# PA_Channel.net
KiCad netlist of a schematic drawn in Altium Designer
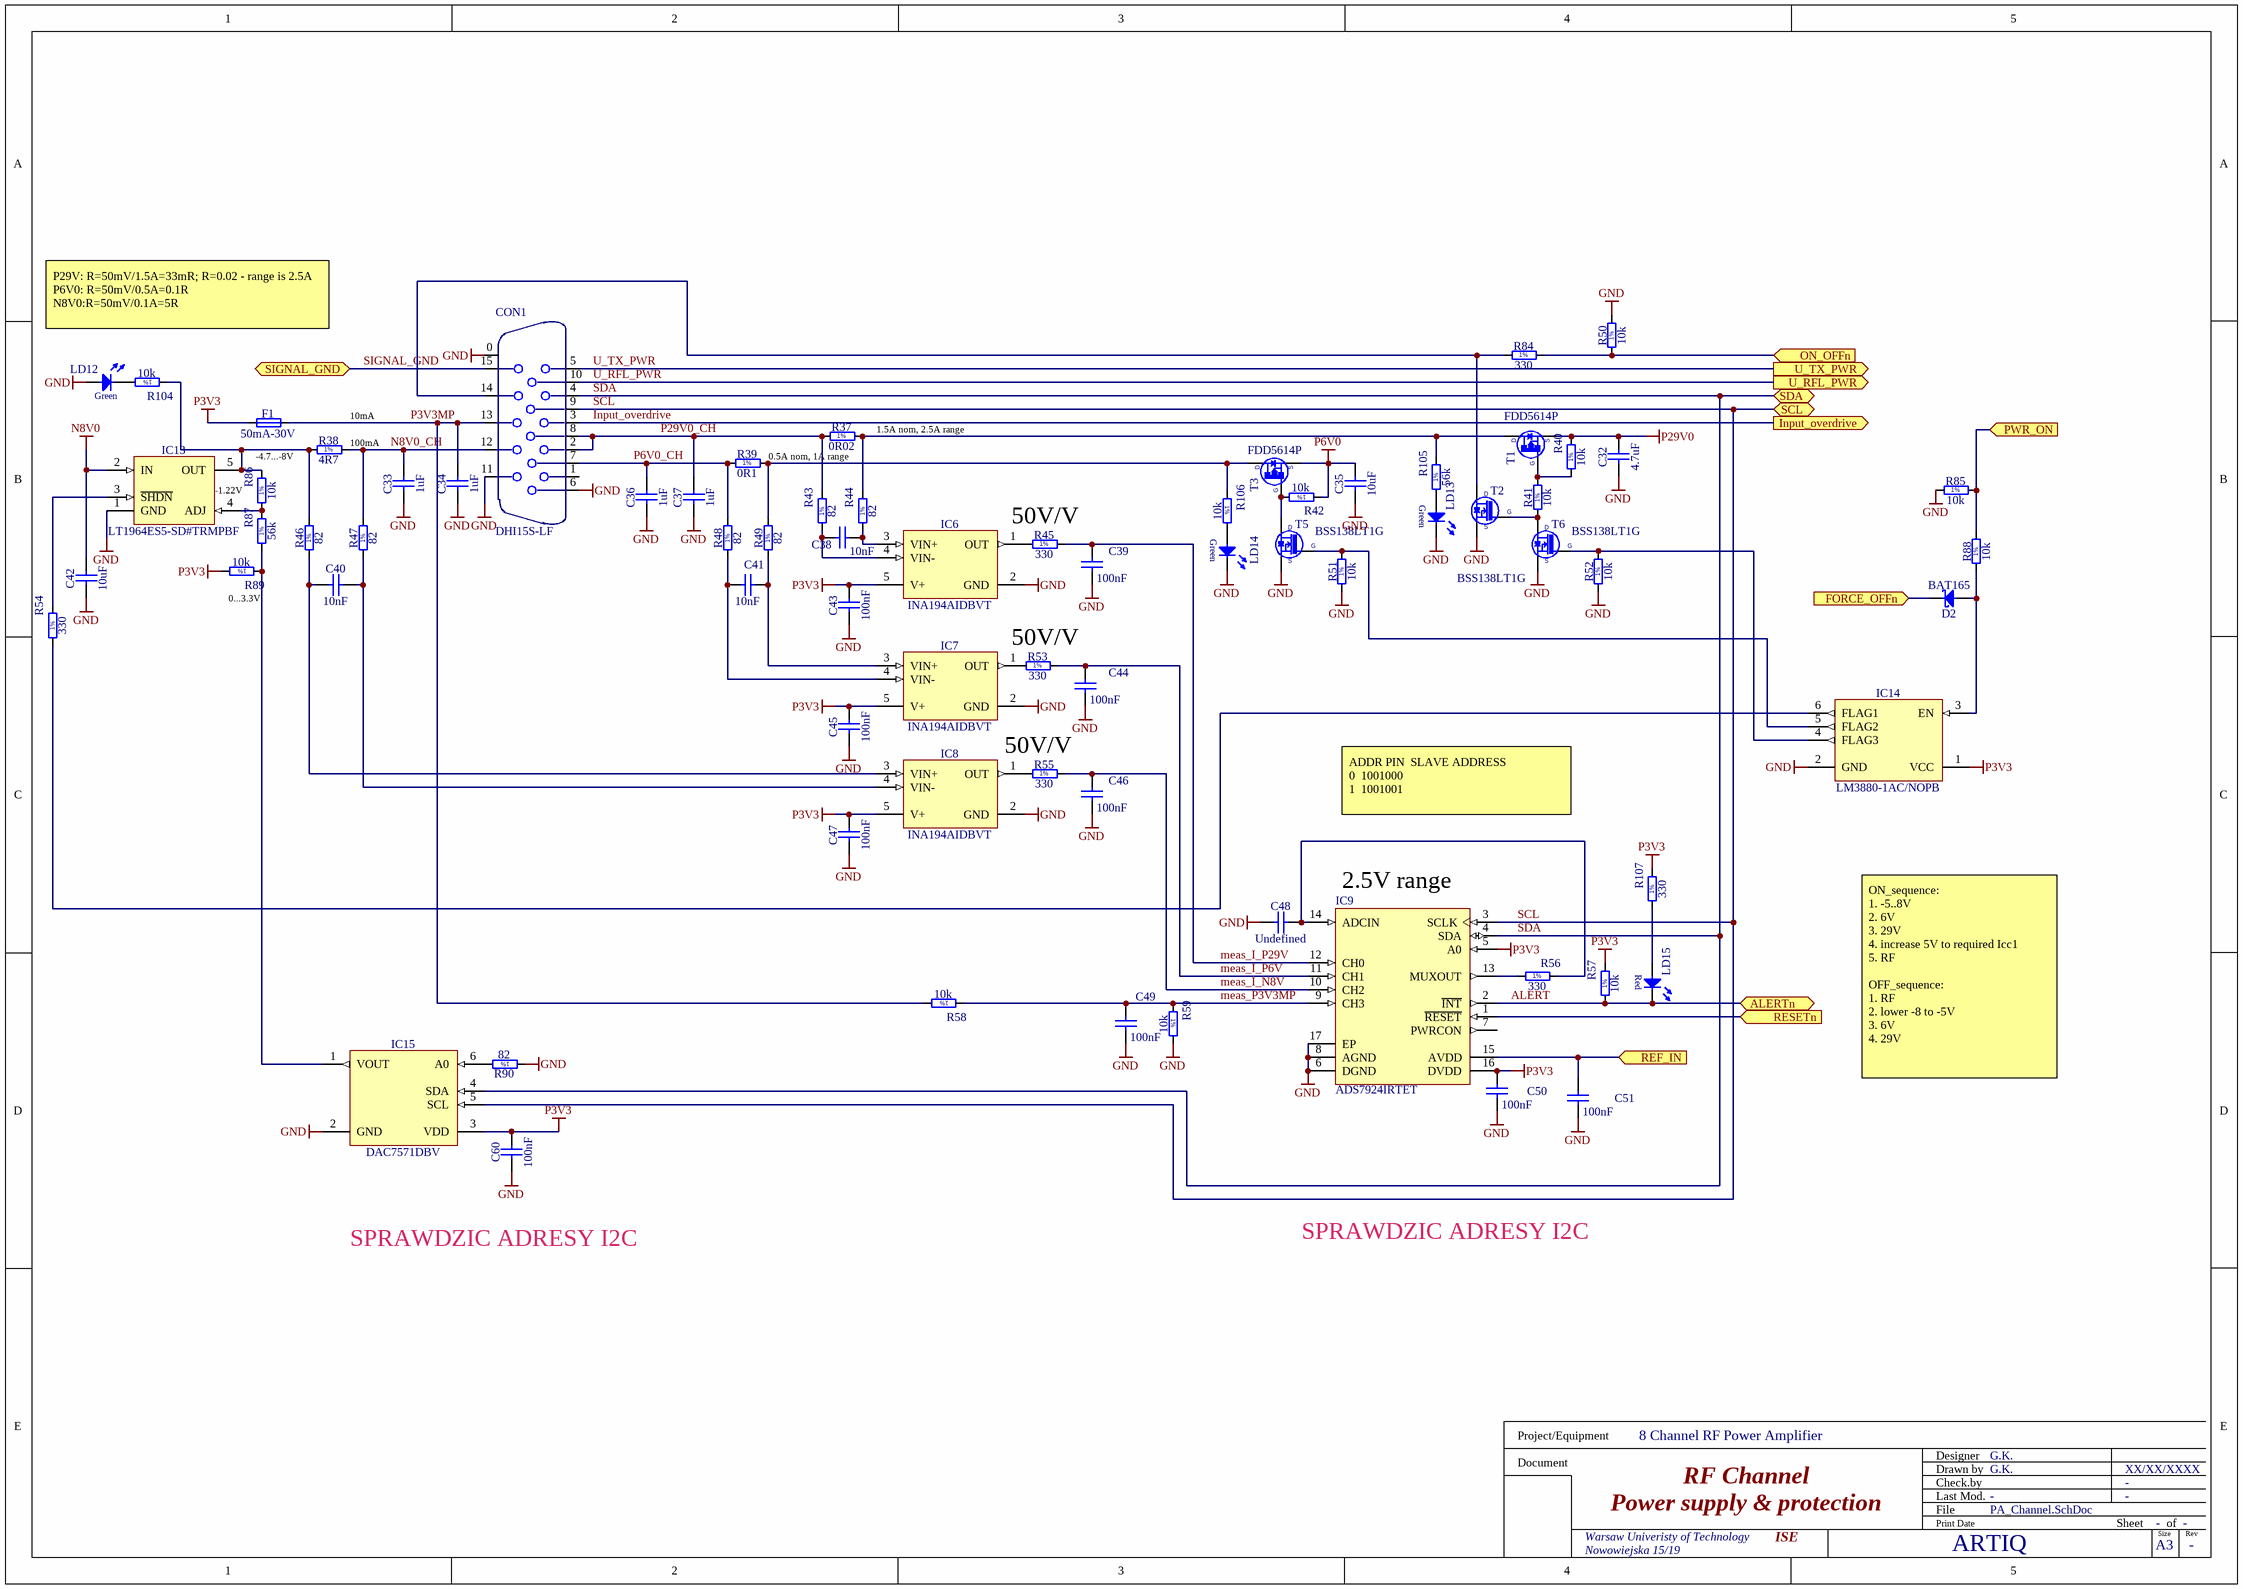
[diagram p0: PA_Channel.SchDoc]

(export (version "E")
  (design (tool "Eeschema 10.0.6"))
  (components
    (comp (ref "C32")
      (value "4.7uF")
      (footprint "CAPC3216X180N")
      (description "Non-polarised capacitor")
      (fields
        (field (name "PART NUMBER") "CC1206_4.7UF_50V_+80%-20%_Y5V")
        (field (name "VOLTAGE") "50V")
        (field (name "AUTHOR") "CERN DEM JLC")
      )
      (libsource (lib "Capacitors") (part "Capacitor - non polarized"))
    )
    (comp (ref "C33")
      (value "1uF")
      (footprint "CAPC2012X110N")
      (description "Non-polarised capacitor")
      (fields
        (field (name "PART NUMBER") "CC0805_1UF_50V_10%_X7R")
        (field (name "VOLTAGE") "50V")
        (field (name "AUTHOR") "CERN DEM JLC")
      )
      (libsource (lib "Capacitors") (part "Capacitor - non polarized"))
    )
    (comp (ref "C34")
      (value "1uF")
      (footprint "CAPC2012X110N")
      (description "Non-polarised capacitor")
      (fields
        (field (name "PART NUMBER") "CC0805_1UF_50V_10%_X7R")
        (field (name "VOLTAGE") "50V")
        (field (name "AUTHOR") "CERN DEM JLC")
      )
      (libsource (lib "Capacitors") (part "Capacitor - non polarized"))
    )
    (comp (ref "C35")
      (value "10uF")
      (footprint "CAPC3216X140N")
      (description "Non-polarised capacitor")
      (fields
        (field (name "PART NUMBER") "CC1206_10UF_16V_10%_X7R")
        (field (name "VOLTAGE") "16V")
        (field (name "AUTHOR") "CERN DEM JLC")
      )
      (libsource (lib "Capacitors") (part "Capacitor - non polarized"))
    )
    (comp (ref "C36")
      (value "1uF")
      (footprint "CAPC2012X110N")
      (description "Non-polarised capacitor")
      (fields
        (field (name "PART NUMBER") "CC0805_1UF_50V_10%_X7R")
        (field (name "VOLTAGE") "50V")
        (field (name "AUTHOR") "CERN DEM JLC")
      )
      (libsource (lib "Capacitors") (part "Capacitor - non polarized"))
    )
    (comp (ref "C37")
      (value "1uF")
      (footprint "CAPC2012X110N")
      (description "Non-polarised capacitor")
      (fields
        (field (name "PART NUMBER") "CC0805_1UF_50V_10%_X7R")
        (field (name "VOLTAGE") "50V")
        (field (name "AUTHOR") "CERN DEM JLC")
      )
      (libsource (lib "Capacitors") (part "Capacitor - non polarized"))
    )
    (comp (ref "C38")
      (value "10nF")
      (footprint "CAPC1608X87N")
      (description "Non-polarised capacitor")
      (fields
        (field (name "PART NUMBER") "CC0603_10NF_50V_5%_C0G")
        (field (name "VOLTAGE") "50V")
        (field (name "AUTHOR") "CERN DEM JLC")
      )
      (libsource (lib "Capacitors") (part "Capacitor - non polarized"))
    )
    (comp (ref "C39")
      (value "100nF")
      (footprint "CAPC1005X55N")
      (description "Non-polarised capacitor")
      (fields
        (field (name "PART NUMBER") "CC0402_100NF_16V_10%_X7R")
        (field (name "VOLTAGE") "16V")
        (field (name "AUTHOR") "CERN DEM JLC")
      )
      (libsource (lib "Capacitors") (part "Capacitor - non polarized"))
    )
    (comp (ref "C40")
      (value "10nF")
      (footprint "CAPC1608X87N")
      (description "Non-polarised capacitor")
      (fields
        (field (name "PART NUMBER") "CC0603_10NF_50V_5%_C0G")
        (field (name "VOLTAGE") "50V")
        (field (name "AUTHOR") "CERN DEM JLC")
      )
      (libsource (lib "Capacitors") (part "Capacitor - non polarized"))
    )
    (comp (ref "C41")
      (value "10nF")
      (footprint "CAPC1608X87N")
      (description "Non-polarised capacitor")
      (fields
        (field (name "PART NUMBER") "CC0603_10NF_50V_5%_C0G")
        (field (name "VOLTAGE") "50V")
        (field (name "AUTHOR") "CERN DEM JLC")
      )
      (libsource (lib "Capacitors") (part "Capacitor - non polarized"))
    )
    (comp (ref "C42")
      (value "10uF")
      (footprint "CAPC3216X140N")
      (description "Non-polarised capacitor")
      (fields
        (field (name "PART NUMBER") "CC1206_10UF_16V_10%_X7R")
        (field (name "VOLTAGE") "16V")
        (field (name "AUTHOR") "CERN DEM JLC")
      )
      (libsource (lib "Capacitors") (part "Capacitor - non polarized"))
    )
    (comp (ref "C43")
      (value "100nF")
      (footprint "CAPC1005X55N")
      (description "Non-polarised capacitor")
      (fields
        (field (name "PART NUMBER") "CC0402_100NF_16V_10%_X7R")
        (field (name "VOLTAGE") "16V")
        (field (name "AUTHOR") "CERN DEM JLC")
      )
      (libsource (lib "Capacitors") (part "Capacitor - non polarized"))
    )
    (comp (ref "C44")
      (value "100nF")
      (footprint "CAPC1005X55N")
      (description "Non-polarised capacitor")
      (fields
        (field (name "PART NUMBER") "CC0402_100NF_16V_10%_X7R")
        (field (name "VOLTAGE") "16V")
        (field (name "AUTHOR") "CERN DEM JLC")
      )
      (libsource (lib "Capacitors") (part "Capacitor - non polarized"))
    )
    (comp (ref "C45")
      (value "100nF")
      (footprint "CAPC1005X55N")
      (description "Non-polarised capacitor")
      (fields
        (field (name "PART NUMBER") "CC0402_100NF_16V_10%_X7R")
        (field (name "VOLTAGE") "16V")
        (field (name "AUTHOR") "CERN DEM JLC")
      )
      (libsource (lib "Capacitors") (part "Capacitor - non polarized"))
    )
    (comp (ref "C46")
      (value "100nF")
      (footprint "CAPC1005X55N")
      (description "Non-polarised capacitor")
      (fields
        (field (name "PART NUMBER") "CC0402_100NF_16V_10%_X7R")
        (field (name "VOLTAGE") "16V")
        (field (name "AUTHOR") "CERN DEM JLC")
      )
      (libsource (lib "Capacitors") (part "Capacitor - non polarized"))
    )
    (comp (ref "C47")
      (value "100nF")
      (footprint "CAPC1005X55N")
      (description "Non-polarised capacitor")
      (fields
        (field (name "PART NUMBER") "CC0402_100NF_16V_10%_X7R")
        (field (name "VOLTAGE") "16V")
        (field (name "AUTHOR") "CERN DEM JLC")
      )
      (libsource (lib "Capacitors") (part "Capacitor - non polarized"))
    )
    (comp (ref "C48")
      (value "Undefined")
      (footprint "CAPC1005X55N")
      (description "Non-polarised capacitor")
      (fields (field (name "PART NUMBER") "CC0402_NO-VALUE") (field (name "AUTHOR") "CERN DEM JLC"))
      (libsource (lib "Capacitors") (part "Capacitor - non polarized"))
    )
    (comp (ref "C49")
      (value "100nF")
      (footprint "CAPC1005X55N")
      (description "Non-polarised capacitor")
      (fields
        (field (name "PART NUMBER") "CC0402_100NF_16V_10%_X7R")
        (field (name "VOLTAGE") "16V")
        (field (name "AUTHOR") "CERN DEM JLC")
      )
      (libsource (lib "Capacitors") (part "Capacitor - non polarized"))
    )
    (comp (ref "C50")
      (value "100nF")
      (footprint "CAPC1005X55N")
      (description "Non-polarised capacitor")
      (fields
        (field (name "PART NUMBER") "CC0402_100NF_16V_10%_X7R")
        (field (name "VOLTAGE") "16V")
        (field (name "AUTHOR") "CERN DEM JLC")
      )
      (libsource (lib "Capacitors") (part "Capacitor - non polarized"))
    )
    (comp (ref "C51")
      (value "100nF")
      (footprint "CAPC1005X55N")
      (description "Non-polarised capacitor")
      (fields
        (field (name "PART NUMBER") "CC0402_100NF_16V_10%_X7R")
        (field (name "VOLTAGE") "16V")
        (field (name "AUTHOR") "CERN DEM JLC")
      )
      (libsource (lib "Capacitors") (part "Capacitor - non polarized"))
    )
    (comp (ref "C60")
      (value "100nF")
      (footprint "CAPC1005X55N")
      (description "Non-polarised capacitor")
      (fields
        (field (name "PART NUMBER") "CC0402_100NF_16V_10%_X7R")
        (field (name "VOLTAGE") "16V")
        (field (name "AUTHOR") "CERN DEM JLC")
      )
      (libsource (lib "Capacitors") (part "Capacitor - non polarized"))
    )
    (comp (ref "CON1")
      (value "DHI15S-LF")
      (footprint "DB15_HD_V_DHI15S-LF")
      (description "High Density D-SUB (Maritex)")
      (libsource (lib "LIBRARY_SCH") (part "CON_DB15HD_F_V"))
    )
    (comp (ref "D2")
      (value "BAT165")
      (footprint "SOD2512X110N")
      (description "Schottky Diode")
      (fields
        (field (name "VOLTAGE") "40V")
        (field (name "POWER") "750mA")
        (field (name "AUTHOR") "CERN DEM JLC")
      )
      (libsource (lib "ICs And Semiconductors") (part "Diode Schottky"))
    )
    (comp (ref "F1")
      (value "50mA-30V")
      (footprint "FUSRC3226X85N")
      (description "Fuse")
      (fields
        (field (name "PART NUMBER") "FUSR1210_TYCO-MICROSMD005F")
        (field (name "MANUFACTURER") "TYCO ELECTRONICS")
        (field (name "AUTHOR") "CERN DEM JLC")
      )
      (libsource (lib "Eletro-mechanical") (part "Fuse"))
    )
    (comp (ref "IC6")
      (value "INA194AIDBVT")
      (footprint "SOT95P280X145-5N")
      (description "Current Shunt Monitor -16V to +80V Common-Mode Range")
      (fields (field (name "MANUFACTURER") "TEXAS INSTRUMENTS") (field (name "AUTHOR") "CERN DEM JLC"))
      (libsource (lib "ICs And Semiconductors") (part "INA194"))
    )
    (comp (ref "IC7")
      (value "INA194AIDBVT")
      (footprint "SOT95P280X145-5N")
      (description "Current Shunt Monitor -16V to +80V Common-Mode Range")
      (fields (field (name "MANUFACTURER") "TEXAS INSTRUMENTS") (field (name "AUTHOR") "CERN DEM JLC"))
      (libsource (lib "ICs And Semiconductors") (part "INA194"))
    )
    (comp (ref "IC8")
      (value "INA194AIDBVT")
      (footprint "SOT95P280X145-5N")
      (description "Current Shunt Monitor -16V to +80V Common-Mode Range")
      (fields (field (name "MANUFACTURER") "TEXAS INSTRUMENTS") (field (name "AUTHOR") "CERN DEM JLC"))
      (libsource (lib "ICs And Semiconductors") (part "INA194"))
    )
    (comp (ref "IC9")
      (value "ADS7924IRTET")
      (footprint "TI-RTE16-1700X1700TP_V")
      (fields (field (name "MANUFACTURER") "Texas Instruments"))
      (libsource (lib "Altium Content Vault") (part "CMP-0003-02162-1"))
    )
    (comp (ref "IC13")
      (value "LT1964ES5-SD#TRMPBF")
      (footprint "SOT95P280X100-5N")
      (description "200mA, Low Noise, Low Dropout Negative Micropower Regulator")
      (fields (field (name "MANUFACTURER") "LINEAR TECHNOLOGY") (field (name "AUTHOR") "CERN DEM JLC"))
      (libsource (lib "ICs And Semiconductors") (part "LT1964-SD"))
    )
    (comp (ref "IC14")
      (value "LM3880-1AC/NOPB")
      (footprint "SOT95P280X145-6N")
      (description "Simple Power Sequencer")
      (fields (field (name "MANUFACTURER") "TEXAS INSTRUMENTS") (field (name "AUTHOR") "CERN DEM MR"))
      (libsource (lib "ICs And Semiconductors") (part "LM3880"))
    )
    (comp (ref "IC15")
      (value "DAC7571DBV")
      (footprint "SOT95P280X145-6N")
      (description "+2.7 V to +5.5 V, I2C Interface (Receive Only), Voltage Output, 12-Bit Digital-To-Analog Converter")
      (fields (field (name "MANUFACTURER") "TEXAS INSTRUMENTS") (field (name "AUTHOR") "CERN DEM MR"))
      (libsource (lib "ICs And Semiconductors") (part "DAC7571"))
    )
    (comp (ref "LD12")
      (value "Green")
      (footprint "LED_OSRAM_LGL29K")
      (description "LED Green 1C 2A")
      (fields
        (field (name "PART NUMBER") "LED_OSRAM_LG L29K-G2J1-24-Z")
        (field (name "MANUFACTURER") "OSRAM")
        (field (name "AUTHOR") "CERN DEM JLC")
      )
      (libsource (lib "ICs And Semiconductors") (part "LED Green 1C 2A"))
    )
    (comp (ref "LD13")
      (value "Green")
      (footprint "LED_OSRAM_LGL29K")
      (description "LED Green 1C 2A")
      (fields
        (field (name "PART NUMBER") "LED_OSRAM_LG L29K-G2J1-24-Z")
        (field (name "MANUFACTURER") "OSRAM")
        (field (name "AUTHOR") "CERN DEM JLC")
      )
      (libsource (lib "ICs And Semiconductors") (part "LED Green 1C 2A"))
    )
    (comp (ref "LD14")
      (value "Green")
      (footprint "LED_OSRAM_LGL29K")
      (description "LED Green 1C 2A")
      (fields
        (field (name "PART NUMBER") "LED_OSRAM_LG L29K-G2J1-24-Z")
        (field (name "MANUFACTURER") "OSRAM")
        (field (name "AUTHOR") "CERN DEM JLC")
      )
      (libsource (lib "ICs And Semiconductors") (part "LED Green 1C 2A"))
    )
    (comp (ref "LD15")
      (value "Super Red")
      (footprint "LED_OSRAM_LS Q976")
      (description "LED Red 1C 2A")
      (fields
        (field (name "PART NUMBER") "LED_OSRAM_LS Q976-NR-1")
        (field (name "MANUFACTURER") "OSRAM")
        (field (name "AUTHOR") "CERN DEM JLC")
      )
      (libsource (lib "ICs And Semiconductors") (part "LED Red 1C 2A"))
    )
    (comp (ref "R37")
      (value "0R02")
      (footprint "RESC3216X80N")
      (description "Resistor - 1%")
      (fields
        (field (name "PART NUMBER") "R1206_0R02_1%_1W_150PPM")
        (field (name "POWER") "1W")
        (field (name "AUTHOR") "CERN DEM JLC")
      )
      (libsource (lib "Resistors") (part "Resistor - 1%"))
    )
    (comp (ref "R38")
      (value "4R7")
      (footprint "RESC3216X65N")
      (description "Resistor - 1%")
      (fields
        (field (name "PART NUMBER") "R1206_4R7_1%_0.25W_200PPM")
        (field (name "POWER") "0.25W")
        (field (name "AUTHOR") "CERN DEM JLC")
      )
      (libsource (lib "Resistors") (part "Resistor - 1%"))
    )
    (comp (ref "R39")
      (value "0R1")
      (footprint "RESC3216X65N")
      (description "Resistor - 1%")
      (fields
        (field (name "PART NUMBER") "R1206_0R1_1%_0.25W_100PPM_YAGEO_PT")
        (field (name "POWER") "0.25W")
        (field (name "AUTHOR") "CERN DEM JMW")
      )
      (libsource (lib "Resistors") (part "Resistor - 1%"))
    )
    (comp (ref "R40")
      (value "10k")
      (footprint "RESC1005X40N")
      (description "Resistor - 1%")
      (fields
        (field (name "PART NUMBER") "R0402_10K_1%_0.0625W_100PPM")
        (field (name "POWER") "0.0625W")
        (field (name "AUTHOR") "CERN DEM JLC")
      )
      (libsource (lib "Resistors") (part "Resistor - 1%"))
    )
    (comp (ref "R41")
      (value "10k")
      (footprint "RESC1005X40N")
      (description "Resistor - 1%")
      (fields
        (field (name "PART NUMBER") "R0402_10K_1%_0.0625W_100PPM")
        (field (name "POWER") "0.0625W")
        (field (name "AUTHOR") "CERN DEM JLC")
      )
      (libsource (lib "Resistors") (part "Resistor - 1%"))
    )
    (comp (ref "R42")
      (value "10k")
      (footprint "RESC1005X40N")
      (description "Resistor - 1%")
      (fields
        (field (name "PART NUMBER") "R0402_10K_1%_0.0625W_100PPM")
        (field (name "POWER") "0.0625W")
        (field (name "AUTHOR") "CERN DEM JLC")
      )
      (libsource (lib "Resistors") (part "Resistor - 1%"))
    )
    (comp (ref "R43")
      (value "82")
      (footprint "RESC1005X40N")
      (description "Resistor - 1%")
      (fields
        (field (name "PART NUMBER") "R0402_82R_1%_0.0625W_100PPM")
        (field (name "POWER") "0.0625W")
        (field (name "AUTHOR") "CERN DEM JLC")
      )
      (libsource (lib "Resistors") (part "Resistor - 1%"))
    )
    (comp (ref "R44")
      (value "82")
      (footprint "RESC1005X40N")
      (description "Resistor - 1%")
      (fields
        (field (name "PART NUMBER") "R0402_82R_1%_0.0625W_100PPM")
        (field (name "POWER") "0.0625W")
        (field (name "AUTHOR") "CERN DEM JLC")
      )
      (libsource (lib "Resistors") (part "Resistor - 1%"))
    )
    (comp (ref "R45")
      (value "330")
      (footprint "RESC1608X55N")
      (description "Resistor - 1%")
      (fields
        (field (name "PART NUMBER") "R0603_330R_1%_0.1W_100PPM")
        (field (name "POWER") "0.1W")
        (field (name "AUTHOR") "CERN DEM JLC")
      )
      (libsource (lib "Resistors") (part "Resistor - 1%"))
    )
    (comp (ref "R46")
      (value "82")
      (footprint "RESC1005X40N")
      (description "Resistor - 1%")
      (fields
        (field (name "PART NUMBER") "R0402_82R_1%_0.0625W_100PPM")
        (field (name "POWER") "0.0625W")
        (field (name "AUTHOR") "CERN DEM JLC")
      )
      (libsource (lib "Resistors") (part "Resistor - 1%"))
    )
    (comp (ref "R47")
      (value "82")
      (footprint "RESC1005X40N")
      (description "Resistor - 1%")
      (fields
        (field (name "PART NUMBER") "R0402_82R_1%_0.0625W_100PPM")
        (field (name "POWER") "0.0625W")
        (field (name "AUTHOR") "CERN DEM JLC")
      )
      (libsource (lib "Resistors") (part "Resistor - 1%"))
    )
    (comp (ref "R48")
      (value "82")
      (footprint "RESC1005X40N")
      (description "Resistor - 1%")
      (fields
        (field (name "PART NUMBER") "R0402_82R_1%_0.0625W_100PPM")
        (field (name "POWER") "0.0625W")
        (field (name "AUTHOR") "CERN DEM JLC")
      )
      (libsource (lib "Resistors") (part "Resistor - 1%"))
    )
    (comp (ref "R49")
      (value "82")
      (footprint "RESC1005X40N")
      (description "Resistor - 1%")
      (fields
        (field (name "PART NUMBER") "R0402_82R_1%_0.0625W_100PPM")
        (field (name "POWER") "0.0625W")
        (field (name "AUTHOR") "CERN DEM JLC")
      )
      (libsource (lib "Resistors") (part "Resistor - 1%"))
    )
    (comp (ref "R50")
      (value "10k")
      (footprint "RESC1005X40N")
      (description "Resistor - 1%")
      (fields
        (field (name "PART NUMBER") "R0402_10K_1%_0.0625W_100PPM")
        (field (name "POWER") "0.0625W")
        (field (name "AUTHOR") "CERN DEM JLC")
      )
      (libsource (lib "Resistors") (part "Resistor - 1%"))
    )
    (comp (ref "R51")
      (value "10k")
      (footprint "RESC1005X40N")
      (description "Resistor - 1%")
      (fields
        (field (name "PART NUMBER") "R0402_10K_1%_0.0625W_100PPM")
        (field (name "POWER") "0.0625W")
        (field (name "AUTHOR") "CERN DEM JLC")
      )
      (libsource (lib "Resistors") (part "Resistor - 1%"))
    )
    (comp (ref "R52")
      (value "10k")
      (footprint "RESC1005X40N")
      (description "Resistor - 1%")
      (fields
        (field (name "PART NUMBER") "R0402_10K_1%_0.0625W_100PPM")
        (field (name "POWER") "0.0625W")
        (field (name "AUTHOR") "CERN DEM JLC")
      )
      (libsource (lib "Resistors") (part "Resistor - 1%"))
    )
    (comp (ref "R53")
      (value "330")
      (footprint "RESC1608X55N")
      (description "Resistor - 1%")
      (fields
        (field (name "PART NUMBER") "R0603_330R_1%_0.1W_100PPM")
        (field (name "POWER") "0.1W")
        (field (name "AUTHOR") "CERN DEM JLC")
      )
      (libsource (lib "Resistors") (part "Resistor - 1%"))
    )
    (comp (ref "R54")
      (value "330")
      (footprint "RESC1608X55N")
      (description "Resistor - 1%")
      (fields
        (field (name "PART NUMBER") "R0603_330R_1%_0.1W_100PPM")
        (field (name "POWER") "0.1W")
        (field (name "AUTHOR") "CERN DEM JLC")
      )
      (libsource (lib "Resistors") (part "Resistor - 1%"))
    )
    (comp (ref "R55")
      (value "330")
      (footprint "RESC1608X55N")
      (description "Resistor - 1%")
      (fields
        (field (name "PART NUMBER") "R0603_330R_1%_0.1W_100PPM")
        (field (name "POWER") "0.1W")
        (field (name "AUTHOR") "CERN DEM JLC")
      )
      (libsource (lib "Resistors") (part "Resistor - 1%"))
    )
    (comp (ref "R56")
      (value "330")
      (footprint "RESC1608X55N")
      (description "Resistor - 1%")
      (fields
        (field (name "PART NUMBER") "R0603_330R_1%_0.1W_100PPM")
        (field (name "POWER") "0.1W")
        (field (name "AUTHOR") "CERN DEM JLC")
      )
      (libsource (lib "Resistors") (part "Resistor - 1%"))
    )
    (comp (ref "R57")
      (value "10k")
      (footprint "RESC1005X40N")
      (description "Resistor - 1%")
      (fields
        (field (name "PART NUMBER") "R0402_10K_1%_0.0625W_100PPM")
        (field (name "POWER") "0.0625W")
        (field (name "AUTHOR") "CERN DEM JLC")
      )
      (libsource (lib "Resistors") (part "Resistor - 1%"))
    )
    (comp (ref "R58")
      (value "10k")
      (footprint "RESC1005X40N")
      (description "Resistor - 1%")
      (fields
        (field (name "PART NUMBER") "R0402_10K_1%_0.0625W_100PPM")
        (field (name "POWER") "0.0625W")
        (field (name "AUTHOR") "CERN DEM JLC")
      )
      (libsource (lib "Resistors") (part "Resistor - 1%"))
    )
    (comp (ref "R59")
      (value "10k")
      (footprint "RESC1005X40N")
      (description "Resistor - 1%")
      (fields
        (field (name "PART NUMBER") "R0402_10K_1%_0.0625W_100PPM")
        (field (name "POWER") "0.0625W")
        (field (name "AUTHOR") "CERN DEM JLC")
      )
      (libsource (lib "Resistors") (part "Resistor - 1%"))
    )
    (comp (ref "R84")
      (value "330")
      (footprint "RESC1608X55N")
      (description "Resistor - 1%")
      (fields
        (field (name "PART NUMBER") "R0603_330R_1%_0.1W_100PPM")
        (field (name "POWER") "0.1W")
        (field (name "AUTHOR") "CERN DEM JLC")
      )
      (libsource (lib "Resistors") (part "Resistor - 1%"))
    )
    (comp (ref "R85")
      (value "10k")
      (footprint "RESC1005X40N")
      (description "Resistor - 1%")
      (fields
        (field (name "PART NUMBER") "R0402_10K_1%_0.0625W_100PPM")
        (field (name "POWER") "0.0625W")
        (field (name "AUTHOR") "CERN DEM JLC")
      )
      (libsource (lib "Resistors") (part "Resistor - 1%"))
    )
    (comp (ref "R86")
      (value "10k")
      (footprint "RESC1005X40N")
      (description "Resistor - 1%")
      (fields
        (field (name "PART NUMBER") "R0402_10K_1%_0.0625W_100PPM")
        (field (name "POWER") "0.0625W")
        (field (name "AUTHOR") "CERN DEM JLC")
      )
      (libsource (lib "Resistors") (part "Resistor - 1%"))
    )
    (comp (ref "R87")
      (value "56k")
      (footprint "RESC1608X55N")
      (description "Resistor - 1%")
      (fields
        (field (name "PART NUMBER") "R0603_56K_1%_0.1W_100PPM")
        (field (name "POWER") "0.1W")
        (field (name "AUTHOR") "CERN DEM JLC")
      )
      (libsource (lib "Resistors") (part "Resistor - 1%"))
    )
    (comp (ref "R88")
      (value "10k")
      (footprint "RESC1005X40N")
      (description "Resistor - 1%")
      (fields
        (field (name "PART NUMBER") "R0402_10K_1%_0.0625W_100PPM")
        (field (name "POWER") "0.0625W")
        (field (name "AUTHOR") "CERN DEM JLC")
      )
      (libsource (lib "Resistors") (part "Resistor - 1%"))
    )
    (comp (ref "R89")
      (value "10k")
      (footprint "RESC1005X40N")
      (description "Resistor - 1%")
      (fields
        (field (name "PART NUMBER") "R0402_10K_1%_0.0625W_100PPM")
        (field (name "POWER") "0.0625W")
        (field (name "AUTHOR") "CERN DEM JLC")
      )
      (libsource (lib "Resistors") (part "Resistor - 1%"))
    )
    (comp (ref "R90")
      (value "82")
      (footprint "RESC1005X40N")
      (description "Resistor - 1%")
      (fields
        (field (name "PART NUMBER") "R0402_82R_1%_0.0625W_100PPM")
        (field (name "POWER") "0.0625W")
        (field (name "AUTHOR") "CERN DEM JLC")
      )
      (libsource (lib "Resistors") (part "Resistor - 1%"))
    )
    (comp (ref "R104")
      (value "10k")
      (footprint "RESC1005X40N")
      (description "Resistor - 1%")
      (fields
        (field (name "PART NUMBER") "R0402_10K_1%_0.0625W_100PPM")
        (field (name "POWER") "0.0625W")
        (field (name "AUTHOR") "CERN DEM JLC")
      )
      (libsource (lib "Resistors") (part "Resistor - 1%"))
    )
    (comp (ref "R105")
      (value "56k")
      (footprint "RESC1608X55N")
      (description "Resistor - 1%")
      (fields
        (field (name "PART NUMBER") "R0603_56K_1%_0.1W_100PPM")
        (field (name "POWER") "0.1W")
        (field (name "AUTHOR") "CERN DEM JLC")
      )
      (libsource (lib "Resistors") (part "Resistor - 1%"))
    )
    (comp (ref "R106")
      (value "10k")
      (footprint "RESC1005X40N")
      (description "Resistor - 1%")
      (fields
        (field (name "PART NUMBER") "R0402_10K_1%_0.0625W_100PPM")
        (field (name "POWER") "0.0625W")
        (field (name "AUTHOR") "CERN DEM JLC")
      )
      (libsource (lib "Resistors") (part "Resistor - 1%"))
    )
    (comp (ref "R107")
      (value "330")
      (footprint "RESC1608X55N")
      (description "Resistor - 1%")
      (fields
        (field (name "PART NUMBER") "R0603_330R_1%_0.1W_100PPM")
        (field (name "POWER") "0.1W")
        (field (name "AUTHOR") "CERN DEM JLC")
      )
      (libsource (lib "Resistors") (part "Resistor - 1%"))
    )
    (comp (ref "T1")
      (value "FDD5614P")
      (footprint "TO228P991X238-3N-R546X521")
      (description "P-CHANNEL MOSFET WITH DIODE")
      (fields (field (name "MANUFACTURER") "FAIRCHILD SEMICONDUCTOR") (field (name "AUTHOR") "CERN DEM JLC"))
      (libsource (lib "ICs And Semiconductors") (part "P-MOSFET-D 1G 2S 3D"))
    )
    (comp (ref "T2")
      (value "BSS138LT1G")
      (footprint "SOT95P240X110-3N")
      (description "N-CHANNEL MOSFET WITH DIODE")
      (fields (field (name "MANUFACTURER") "ON SEMICONDUCTOR") (field (name "AUTHOR") "CERN DEM JLC"))
      (libsource (lib "ICs And Semiconductors") (part "N-MOSFET-D 1G 2S 3D"))
    )
    (comp (ref "T3")
      (value "FDD5614P")
      (footprint "TO228P991X238-3N-R546X521")
      (description "P-CHANNEL MOSFET WITH DIODE")
      (fields (field (name "MANUFACTURER") "FAIRCHILD SEMICONDUCTOR") (field (name "AUTHOR") "CERN DEM JLC"))
      (libsource (lib "ICs And Semiconductors") (part "P-MOSFET-D 1G 2S 3D"))
    )
    (comp (ref "T5")
      (value "BSS138LT1G")
      (footprint "SOT95P240X110-3N")
      (description "N-CHANNEL MOSFET WITH DIODE")
      (fields (field (name "MANUFACTURER") "ON SEMICONDUCTOR") (field (name "AUTHOR") "CERN DEM JLC"))
      (libsource (lib "ICs And Semiconductors") (part "N-MOSFET-D 1G 2S 3D"))
    )
    (comp (ref "T6")
      (value "BSS138LT1G")
      (footprint "SOT95P240X110-3N")
      (description "N-CHANNEL MOSFET WITH DIODE")
      (fields (field (name "MANUFACTURER") "ON SEMICONDUCTOR") (field (name "AUTHOR") "CERN DEM JLC"))
      (libsource (lib "ICs And Semiconductors") (part "N-MOSFET-D 1G 2S 3D"))
    )
  )
  (nets
    (net (code "1") (name "/ALERT") (class "Default")
      (node (ref "IC9") (pin "2") (pinfunction "~{INT}_2") (pintype "output"))
      (node (ref "LD15") (pin "1") (pinfunction "C_1") (pintype "passive"))
      (node (ref "R57") (pin "1") (pinfunction "1_1") (pintype "passive"))
    )
    (net (code "2") (name "/FORCE_OFFn") (class "Default")
      (node (ref "D2") (pin "1") (pinfunction "C_1") (pintype "passive"))
    )
    (net (code "3") (name "/Input_overdrive") (class "Default")
      (node (ref "CON1") (pin "3") (pintype "passive"))
    )
    (net (code "4") (name "/N8V0_CH") (class "Default")
      (node (ref "C33") (pin "2") (pinfunction "2_2") (pintype "passive"))
      (node (ref "CON1") (pin "12") (pintype "passive"))
      (node (ref "R38") (pin "2") (pinfunction "2_2") (pintype "passive"))
      (node (ref "R47") (pin "2") (pinfunction "2_2") (pintype "passive"))
    )
    (net (code "5") (name "/ON_OFFn") (class "Default")
      (node (ref "R50") (pin "1") (pinfunction "1_1") (pintype "passive"))
      (node (ref "R84") (pin "2") (pinfunction "2_2") (pintype "passive"))
    )
    (net (code "6") (name "/P3V3MP") (class "Default")
      (node (ref "C34") (pin "2") (pinfunction "2_2") (pintype "passive"))
      (node (ref "CON1") (pin "13") (pintype "passive"))
      (node (ref "F1") (pin "2") (pinfunction "2_2") (pintype "passive"))
      (node (ref "R58") (pin "2") (pinfunction "2_2") (pintype "passive"))
    )
    (net (code "7") (name "/P6V0_CH") (class "Default")
      (node (ref "C36") (pin "2") (pinfunction "2_2") (pintype "passive"))
      (node (ref "CON1") (pin "7") (pintype "passive"))
      (node (ref "R39") (pin "1") (pinfunction "1_1") (pintype "passive"))
      (node (ref "R48") (pin "2") (pinfunction "2_2") (pintype "passive"))
    )
    (net (code "8") (name "/P29V0_CH") (class "Default")
      (node (ref "C37") (pin "2") (pinfunction "2_2") (pintype "passive"))
      (node (ref "CON1") (pin "2") (pintype "passive"))
      (node (ref "CON1") (pin "8") (pintype "passive"))
      (node (ref "R37") (pin "1") (pinfunction "1_1") (pintype "passive"))
      (node (ref "R43") (pin "2") (pinfunction "2_2") (pintype "passive"))
    )
    (net (code "9") (name "/PWR_ON") (class "Default")
      (node (ref "R85") (pin "2") (pinfunction "2_2") (pintype "passive"))
      (node (ref "R88") (pin "2") (pinfunction "2_2") (pintype "passive"))
    )
    (net (code "10") (name "/REF_IN") (class "Default")
      (node (ref "C51") (pin "1") (pinfunction "1_1") (pintype "passive"))
      (node (ref "IC9") (pin "15") (pinfunction "AVDD_15") (pintype "power_in"))
    )
    (net (code "11") (name "/RESETn") (class "Default")
      (node (ref "IC9") (pin "1") (pinfunction "~{RESET}_1") (pintype "input"))
    )
    (net (code "12") (name "/SCL") (class "Default")
      (node (ref "CON1") (pin "9") (pintype "passive"))
      (node (ref "IC15") (pin "5") (pinfunction "SCL_5") (pintype "input"))
      (node (ref "IC9") (pin "3") (pinfunction "SCLK_3") (pintype "input"))
    )
    (net (code "13") (name "/SDA") (class "Default")
      (node (ref "CON1") (pin "4") (pintype "passive"))
      (node (ref "IC15") (pin "4") (pinfunction "SDA_4") (pintype "input"))
      (node (ref "IC9") (pin "4") (pinfunction "SDA_4") (pintype "bidirectional"))
    )
    (net (code "14") (name "/SIGNAL_GND") (class "Default")
      (node (ref "CON1") (pin "15") (pintype "passive"))
    )
    (net (code "15") (name "/U_RFL_PWR") (class "Default") (node (ref "CON1") (pin "10") (pintype "passive")))
    (net (code "16") (name "/U_TX_PWR") (class "Default") (node (ref "CON1") (pin "5") (pintype "passive")))
    (net (code "17") (name "/meas_I_N8V") (class "Default")
      (node (ref "C46") (pin "1") (pinfunction "1_1") (pintype "passive"))
      (node (ref "IC9") (pin "10") (pinfunction "CH2_10") (pintype "input"))
      (node (ref "R55") (pin "2") (pinfunction "2_2") (pintype "passive"))
    )
    (net (code "18") (name "/meas_I_P6V") (class "Default")
      (node (ref "C44") (pin "1") (pinfunction "1_1") (pintype "passive"))
      (node (ref "IC9") (pin "11") (pinfunction "CH1_11") (pintype "input"))
      (node (ref "R53") (pin "2") (pinfunction "2_2") (pintype "passive"))
    )
    (net (code "19") (name "/meas_I_P29V") (class "Default")
      (node (ref "C39") (pin "1") (pinfunction "1_1") (pintype "passive"))
      (node (ref "IC9") (pin "12") (pinfunction "CH0_12") (pintype "input"))
      (node (ref "R45") (pin "2") (pinfunction "2_2") (pintype "passive"))
    )
    (net (code "20") (name "/meas_P3V3MP") (class "Default")
      (node (ref "C49") (pin "1") (pinfunction "1_1") (pintype "passive"))
      (node (ref "IC9") (pin "9") (pinfunction "CH3_9") (pintype "input"))
      (node (ref "R58") (pin "1") (pinfunction "1_1") (pintype "passive"))
      (node (ref "R59") (pin "1") (pinfunction "1_1") (pintype "passive"))
    )
    (net (code "21") (name "GND") (class "Default")
      (node (ref "C32") (pin "1") (pinfunction "1_1") (pintype "passive"))
      (node (ref "C33") (pin "1") (pinfunction "1_1") (pintype "passive"))
      (node (ref "C34") (pin "1") (pinfunction "1_1") (pintype "passive"))
      (node (ref "C35") (pin "1") (pinfunction "1_1") (pintype "passive"))
      (node (ref "C36") (pin "1") (pinfunction "1_1") (pintype "passive"))
      (node (ref "C37") (pin "1") (pinfunction "1_1") (pintype "passive"))
      (node (ref "C39") (pin "2") (pinfunction "2_2") (pintype "passive"))
      (node (ref "C42") (pin "1") (pinfunction "1_1") (pintype "passive"))
      (node (ref "C43") (pin "1") (pinfunction "1_1") (pintype "passive"))
      (node (ref "C44") (pin "2") (pinfunction "2_2") (pintype "passive"))
      (node (ref "C45") (pin "1") (pinfunction "1_1") (pintype "passive"))
      (node (ref "C46") (pin "2") (pinfunction "2_2") (pintype "passive"))
      (node (ref "C47") (pin "1") (pinfunction "1_1") (pintype "passive"))
      (node (ref "C48") (pin "1") (pinfunction "1_1") (pintype "passive"))
      (node (ref "C49") (pin "2") (pinfunction "2_2") (pintype "passive"))
      (node (ref "C50") (pin "2") (pinfunction "2_2") (pintype "passive"))
      (node (ref "C51") (pin "2") (pinfunction "2_2") (pintype "passive"))
      (node (ref "C60") (pin "1") (pinfunction "1_1") (pintype "passive"))
      (node (ref "CON1") (pin "0") (pintype "passive"))
      (node (ref "CON1") (pin "11") (pintype "passive"))
      (node (ref "CON1") (pin "6") (pintype "passive"))
      (node (ref "IC13") (pin "1") (pinfunction "GND_1") (pintype "power_in"))
      (node (ref "IC14") (pin "2") (pinfunction "GND_2") (pintype "power_in"))
      (node (ref "IC15") (pin "2") (pinfunction "GND_2") (pintype "power_in"))
      (node (ref "IC6") (pin "2") (pinfunction "GND_2") (pintype "power_in"))
      (node (ref "IC7") (pin "2") (pinfunction "GND_2") (pintype "power_in"))
      (node (ref "IC8") (pin "2") (pinfunction "GND_2") (pintype "power_in"))
      (node (ref "IC9") (pin "17") (pinfunction "EP_17") (pintype "power_in"))
      (node (ref "IC9") (pin "6") (pinfunction "DGND_6") (pintype "power_in"))
      (node (ref "IC9") (pin "8") (pinfunction "AGND_8") (pintype "power_in"))
      (node (ref "LD12") (pin "2") (pinfunction "A_2") (pintype "passive"))
      (node (ref "LD13") (pin "1") (pinfunction "C_1") (pintype "passive"))
      (node (ref "LD14") (pin "1") (pinfunction "C_1") (pintype "passive"))
      (node (ref "R50") (pin "2") (pinfunction "2_2") (pintype "passive"))
      (node (ref "R51") (pin "1") (pinfunction "1_1") (pintype "passive"))
      (node (ref "R52") (pin "1") (pinfunction "1_1") (pintype "passive"))
      (node (ref "R59") (pin "2") (pinfunction "2_2") (pintype "passive"))
      (node (ref "R85") (pin "1") (pinfunction "1_1") (pintype "passive"))
      (node (ref "R90") (pin "1") (pinfunction "1_1") (pintype "passive"))
      (node (ref "T2") (pin "2") (pinfunction "S_2") (pintype "passive"))
      (node (ref "T5") (pin "2") (pinfunction "S_2") (pintype "passive"))
      (node (ref "T6") (pin "2") (pinfunction "S_2") (pintype "passive"))
    )
    (net (code "22") (name "N8V0") (class "Default")
      (node (ref "C42") (pin "2") (pinfunction "2_2") (pintype "passive"))
      (node (ref "IC13") (pin "2") (pinfunction "IN_2") (pintype "input"))
    )
    (net (code "23") (name "Net-(D2-A)") (class "Default")
      (node (ref "D2") (pin "2") (pinfunction "A_2") (pintype "passive"))
      (node (ref "IC14") (pin "3") (pinfunction "EN_3") (pintype "input"))
      (node (ref "R88") (pin "1") (pinfunction "1_1") (pintype "passive"))
    )
    (net (code "24") (name "Net-(IC6-OUT)") (class "Default")
      (node (ref "IC6") (pin "1") (pinfunction "OUT_1") (pintype "output"))
      (node (ref "R45") (pin "1") (pinfunction "1_1") (pintype "passive"))
    )
    (net (code "25") (name "Net-(IC6-VIN+)") (class "Default")
      (node (ref "C38") (pin "2") (pinfunction "2_2") (pintype "passive"))
      (node (ref "IC6") (pin "3") (pinfunction "VIN+_3") (pintype "input"))
      (node (ref "R44") (pin "1") (pinfunction "1_1") (pintype "passive"))
    )
    (net (code "26") (name "Net-(IC6-VIN-)") (class "Default")
      (node (ref "C38") (pin "1") (pinfunction "1_1") (pintype "passive"))
      (node (ref "IC6") (pin "4") (pinfunction "VIN-_4") (pintype "input"))
      (node (ref "R43") (pin "1") (pinfunction "1_1") (pintype "passive"))
    )
    (net (code "27") (name "Net-(IC7-VIN+)") (class "Default")
      (node (ref "C41") (pin "2") (pinfunction "2_2") (pintype "passive"))
      (node (ref "IC7") (pin "3") (pinfunction "VIN+_3") (pintype "input"))
      (node (ref "R49") (pin "1") (pinfunction "1_1") (pintype "passive"))
    )
    (net (code "28") (name "Net-(IC7-VIN-)") (class "Default")
      (node (ref "C41") (pin "1") (pinfunction "1_1") (pintype "passive"))
      (node (ref "IC7") (pin "4") (pinfunction "VIN-_4") (pintype "input"))
      (node (ref "R48") (pin "1") (pinfunction "1_1") (pintype "passive"))
    )
    (net (code "29") (name "Net-(IC8-OUT)") (class "Default")
      (node (ref "IC8") (pin "1") (pinfunction "OUT_1") (pintype "output"))
      (node (ref "R55") (pin "1") (pinfunction "1_1") (pintype "passive"))
    )
    (net (code "30") (name "Net-(IC8-VIN+)") (class "Default")
      (node (ref "C40") (pin "1") (pinfunction "1_1") (pintype "passive"))
      (node (ref "IC8") (pin "3") (pinfunction "VIN+_3") (pintype "input"))
      (node (ref "R46") (pin "1") (pinfunction "1_1") (pintype "passive"))
    )
    (net (code "31") (name "Net-(IC8-VIN-)") (class "Default")
      (node (ref "C40") (pin "2") (pinfunction "2_2") (pintype "passive"))
      (node (ref "IC8") (pin "4") (pinfunction "VIN-_4") (pintype "input"))
      (node (ref "R47") (pin "1") (pinfunction "1_1") (pintype "passive"))
    )
    (net (code "32") (name "Net-(IC9-ADCIN)") (class "Default")
      (node (ref "C48") (pin "2") (pinfunction "2_2") (pintype "passive"))
      (node (ref "IC9") (pin "14") (pinfunction "ADCIN_14") (pintype "input"))
      (node (ref "R56") (pin "2") (pinfunction "2_2") (pintype "passive"))
    )
    (net (code "33") (name "Net-(IC9-MUXOUT)") (class "Default")
      (node (ref "IC9") (pin "13") (pinfunction "MUXOUT_13") (pintype "output"))
      (node (ref "R56") (pin "1") (pinfunction "1_1") (pintype "passive"))
    )
    (net (code "34") (name "Net-(IC13-ADJ)") (class "Default")
      (node (ref "IC13") (pin "4") (pinfunction "ADJ_4") (pintype "input"))
      (node (ref "R86") (pin "1") (pinfunction "1_1") (pintype "passive"))
      (node (ref "R87") (pin "2") (pinfunction "2_2") (pintype "passive"))
    )
    (net (code "35") (name "Net-(IC13-OUT)") (class "Default")
      (node (ref "IC13") (pin "5") (pinfunction "OUT_5") (pintype "power_in"))
      (node (ref "R104") (pin "1") (pinfunction "1_1") (pintype "passive"))
      (node (ref "R38") (pin "1") (pinfunction "1_1") (pintype "passive"))
      (node (ref "R46") (pin "2") (pinfunction "2_2") (pintype "passive"))
      (node (ref "R86") (pin "2") (pinfunction "2_2") (pintype "passive"))
    )
    (net (code "36") (name "Net-(IC13-~{SHDN})") (class "Default")
      (node (ref "IC13") (pin "3") (pinfunction "~{SHDN}_3") (pintype "input"))
      (node (ref "R54") (pin "2") (pinfunction "2_2") (pintype "passive"))
    )
    (net (code "37") (name "Net-(IC14-FLAG1)") (class "Default")
      (node (ref "IC14") (pin "6") (pinfunction "FLAG1_6") (pintype "output"))
      (node (ref "R54") (pin "1") (pinfunction "1_1") (pintype "passive"))
    )
    (net (code "38") (name "Net-(IC14-FLAG2)") (class "Default")
      (node (ref "IC14") (pin "5") (pinfunction "FLAG2_5") (pintype "output"))
      (node (ref "R51") (pin "2") (pinfunction "2_2") (pintype "passive"))
      (node (ref "T5") (pin "1") (pinfunction "G_1") (pintype "passive"))
    )
    (net (code "39") (name "Net-(IC14-FLAG3)") (class "Default")
      (node (ref "IC14") (pin "4") (pinfunction "FLAG3_4") (pintype "output"))
      (node (ref "R52") (pin "2") (pinfunction "2_2") (pintype "passive"))
      (node (ref "T6") (pin "1") (pinfunction "G_1") (pintype "passive"))
    )
    (net (code "40") (name "Net-(IC15-A0)") (class "Default")
      (node (ref "IC15") (pin "6") (pinfunction "A0_6") (pintype "input"))
      (node (ref "R90") (pin "2") (pinfunction "2_2") (pintype "passive"))
    )
    (net (code "41") (name "Net-(IC15-VOUT)") (class "Default")
      (node (ref "IC15") (pin "1") (pinfunction "VOUT_1") (pintype "output"))
      (node (ref "R87") (pin "1") (pinfunction "1_1") (pintype "passive"))
      (node (ref "R89") (pin "1") (pinfunction "1_1") (pintype "passive"))
    )
    (net (code "42") (name "Net-(LD12-C)") (class "Default")
      (node (ref "LD12") (pin "1") (pinfunction "C_1") (pintype "passive"))
      (node (ref "R104") (pin "2") (pinfunction "2_2") (pintype "passive"))
    )
    (net (code "43") (name "Net-(LD13-A)") (class "Default")
      (node (ref "LD13") (pin "2") (pinfunction "A_2") (pintype "passive"))
      (node (ref "R105") (pin "1") (pinfunction "1_1") (pintype "passive"))
    )
    (net (code "44") (name "Net-(LD14-A)") (class "Default")
      (node (ref "LD14") (pin "2") (pinfunction "A_2") (pintype "passive"))
      (node (ref "R106") (pin "2") (pinfunction "2_2") (pintype "passive"))
    )
    (net (code "45") (name "Net-(LD15-A)") (class "Default")
      (node (ref "LD15") (pin "2") (pinfunction "A_2") (pintype "passive"))
      (node (ref "R107") (pin "1") (pinfunction "1_1") (pintype "passive"))
    )
    (net (code "46") (name "Net-(T1-D)") (class "Default")
      (node (ref "R105") (pin "2") (pinfunction "2_2") (pintype "passive"))
      (node (ref "R37") (pin "2") (pinfunction "2_2") (pintype "passive"))
      (node (ref "R44") (pin "2") (pinfunction "2_2") (pintype "passive"))
      (node (ref "T1") (pin "3") (pinfunction "D_3") (pintype "passive"))
    )
    (net (code "47") (name "Net-(T1-G)") (class "Default")
      (node (ref "R40") (pin "1") (pinfunction "1_1") (pintype "passive"))
      (node (ref "R41") (pin "2") (pinfunction "2_2") (pintype "passive"))
      (node (ref "T1") (pin "1") (pinfunction "G_1") (pintype "passive"))
    )
    (net (code "48") (name "Net-(T2-D)") (class "Default")
      (node (ref "CON1") (pin "14") (pintype "passive"))
      (node (ref "R84") (pin "1") (pinfunction "1_1") (pintype "passive"))
      (node (ref "T2") (pin "3") (pinfunction "D_3") (pintype "passive"))
    )
    (net (code "49") (name "Net-(T2-G)") (class "Default")
      (node (ref "R41") (pin "1") (pinfunction "1_1") (pintype "passive"))
      (node (ref "T2") (pin "1") (pinfunction "G_1") (pintype "passive"))
      (node (ref "T6") (pin "3") (pinfunction "D_3") (pintype "passive"))
    )
    (net (code "50") (name "Net-(T3-D)") (class "Default")
      (node (ref "R106") (pin "1") (pinfunction "1_1") (pintype "passive"))
      (node (ref "R39") (pin "2") (pinfunction "2_2") (pintype "passive"))
      (node (ref "R49") (pin "2") (pinfunction "2_2") (pintype "passive"))
      (node (ref "T3") (pin "3") (pinfunction "D_3") (pintype "passive"))
    )
    (net (code "51") (name "Net-(T3-G)") (class "Default")
      (node (ref "R42") (pin "2") (pinfunction "2_2") (pintype "passive"))
      (node (ref "T3") (pin "1") (pinfunction "G_1") (pintype "passive"))
      (node (ref "T5") (pin "3") (pinfunction "D_3") (pintype "passive"))
    )
    (net (code "52") (name "P3V3") (class "Default")
      (node (ref "C43") (pin "2") (pinfunction "2_2") (pintype "passive"))
      (node (ref "C45") (pin "2") (pinfunction "2_2") (pintype "passive"))
      (node (ref "C47") (pin "2") (pinfunction "2_2") (pintype "passive"))
      (node (ref "C50") (pin "1") (pinfunction "1_1") (pintype "passive"))
      (node (ref "C60") (pin "2") (pinfunction "2_2") (pintype "passive"))
      (node (ref "F1") (pin "1") (pinfunction "1_1") (pintype "passive"))
      (node (ref "IC14") (pin "1") (pinfunction "VCC_1") (pintype "power_in"))
      (node (ref "IC15") (pin "3") (pinfunction "VDD_3") (pintype "power_in"))
      (node (ref "IC6") (pin "5") (pinfunction "V+_5") (pintype "power_in"))
      (node (ref "IC7") (pin "5") (pinfunction "V+_5") (pintype "power_in"))
      (node (ref "IC8") (pin "5") (pinfunction "V+_5") (pintype "power_in"))
      (node (ref "IC9") (pin "16") (pinfunction "DVDD_16") (pintype "power_in"))
      (node (ref "IC9") (pin "5") (pinfunction "A0_5") (pintype "input"))
      (node (ref "R107") (pin "2") (pinfunction "2_2") (pintype "passive"))
      (node (ref "R57") (pin "2") (pinfunction "2_2") (pintype "passive"))
      (node (ref "R89") (pin "2") (pinfunction "2_2") (pintype "passive"))
    )
    (net (code "53") (name "P6V0") (class "Default")
      (node (ref "C35") (pin "2") (pinfunction "2_2") (pintype "passive"))
      (node (ref "R42") (pin "1") (pinfunction "1_1") (pintype "passive"))
      (node (ref "T3") (pin "2") (pinfunction "S_2") (pintype "passive"))
    )
    (net (code "54") (name "P29V0") (class "Default")
      (node (ref "C32") (pin "2") (pinfunction "2_2") (pintype "passive"))
      (node (ref "R40") (pin "2") (pinfunction "2_2") (pintype "passive"))
      (node (ref "T1") (pin "2") (pinfunction "S_2") (pintype "passive"))
    )
    (net (code "55") (name "unconnected-(CON1-Pad1)") (class "Default")
      (node (ref "CON1") (pin "1") (pintype "passive"))
    )
    (net (code "56") (name "unconnected-(IC7-OUT-Pad1)") (class "Default")
      (node (ref "IC7") (pin "1") (pinfunction "OUT_1") (pintype "output"))
    )
    (net (code "57") (name "unconnected-(IC9-PWRCON-Pad7)") (class "Default")
      (node (ref "IC9") (pin "7") (pinfunction "PWRCON_7") (pintype "output"))
    )
    (net (code "58") (name "unconnected-(R53-Pad1)") (class "Default")
      (node (ref "R53") (pin "1") (pinfunction "1_1") (pintype "passive"))
    )
  )
)
